# Main_9.net
KiCad netlist of a schematic drawn in Altium Designer
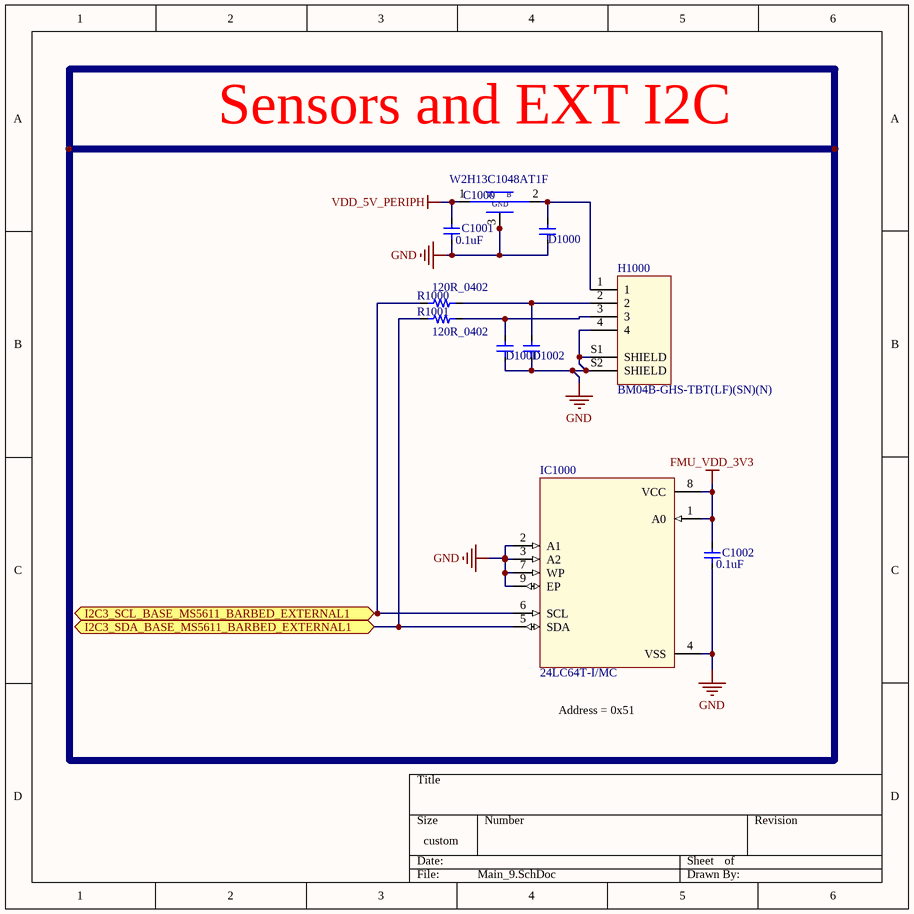
[diagram p0: Main_9.SchDoc]

(export (version "E")
  (design (tool "Eeschema 10.0.6"))
  (components
    (comp (ref "C1000")
      (value "W2H13C1048AT1F")
      (footprint "W2H13C1048AT1F")
      (description "Feed Through Capacitors 25V 0.1uF X7R")
      (libsource (lib "UAV_mainboard") (part "W2H13C1048AT1F"))
    )
    (comp (ref "C1001")
      (value "0.1uF")
      (footprint "C0603")
      (description "CAP CER 0.1UF 25V X7R 0603")
      (libsource (lib "UAV_mainboard") (part "CC0603KRX7R8BB104"))
    )
    (comp (ref "C1002")
      (value "0.1uF")
      (footprint "C0603")
      (description "CAP CER 0.1UF 25V X7R 0603")
      (libsource (lib "UAV_mainboard") (part "CC0603KRX7R8BB104"))
    )
    (comp (ref "D1000")
      (value "PESD0402-140")
      (footprint "PESD0402-140")
      (description "40V Clamp - Ipp Tvs Diode Surface Mount 0402")
      (libsource (lib "UAV_mainboard") (part "PESD0402-140"))
    )
    (comp (ref "D1001")
      (value "PESD0402-140")
      (footprint "PESD0402-140")
      (description "40V Clamp - Ipp Tvs Diode Surface Mount 0402")
      (libsource (lib "UAV_mainboard") (part "PESD0402-140"))
    )
    (comp (ref "D1002")
      (value "PESD0402-140")
      (footprint "PESD0402-140")
      (description "40V Clamp - Ipp Tvs Diode Surface Mount 0402")
      (libsource (lib "UAV_mainboard") (part "PESD0402-140"))
    )
    (comp (ref "H1000")
      (value "BM04B-GHS-TBT(LF)(SN)(N)")
      (footprint "BM04B-GHS-TBT(LF)(SN)(N)")
      (description "Connector Header Surface Mount 4 position 0.049\" (1.25mm)")
      (libsource (lib "UAV_mainboard") (part "BM04B-GHS-TBT(LF)(SN)(N)"))
    )
    (comp (ref "IC1000")
      (value "24LC64T-I/MC")
      (footprint "8DFN")
      (description "IC EEPROM 64KBIT I2C 400KHZ 8DFN")
      (libsource (lib "UAV_mainboard") (part "24LC64T-I/MC"))
    )
    (comp (ref "R1000")
      (value "120R_0402")
      (footprint "R0402")
      (description "120 Ohms ±1% 0.063W, 1/16W Chip Resistor 0402 (1005 Metric) Moisture Resistant Thick Film")
      (libsource (lib "UAV_mainboard") (part "RC0402FR-07120RL"))
    )
    (comp (ref "R1001")
      (value "120R_0402")
      (footprint "R0402")
      (description "120 Ohms ±1% 0.063W, 1/16W Chip Resistor 0402 (1005 Metric) Moisture Resistant Thick Film")
      (libsource (lib "UAV_mainboard") (part "RC0402FR-07120RL"))
    )
  )
  (nets
    (net (code "1") (name "/I2C3_SCL_BASE_MS5611_BARBED_EXTERNAL1") (class "Default")
      (node (ref "IC1000") (pin "6") (pinfunction "SCL_6") (pintype "input"))
      (node (ref "R1000") (pin "1") (pinfunction "1_1") (pintype "passive"))
    )
    (net (code "2") (name "/I2C3_SDA_BASE_MS5611_BARBED_EXTERNAL1") (class "Default")
      (node (ref "IC1000") (pin "5") (pinfunction "SDA_5") (pintype "bidirectional"))
      (node (ref "R1001") (pin "1") (pinfunction "1_1") (pintype "passive"))
    )
    (net (code "3") (name "FMU_VDD_3V3") (class "Default")
      (node (ref "C1002") (pin "2") (pinfunction "2_2") (pintype "passive"))
      (node (ref "IC1000") (pin "1") (pinfunction "A0_1") (pintype "input"))
      (node (ref "IC1000") (pin "8") (pinfunction "VCC_8") (pintype "power_in"))
    )
    (net (code "4") (name "GND") (class "Default")
      (node (ref "C1000") (pin "3") (pintype "passive"))
      (node (ref "C1000") (pin "4") (pinfunction "4_4") (pintype "passive"))
      (node (ref "C1001") (pin "1") (pinfunction "1_1") (pintype "passive"))
      (node (ref "C1002") (pin "1") (pinfunction "1_1") (pintype "passive"))
      (node (ref "D1000") (pin "1") (pinfunction "1_1") (pintype "passive"))
      (node (ref "D1001") (pin "1") (pinfunction "1_1") (pintype "passive"))
      (node (ref "D1002") (pin "1") (pinfunction "1_1") (pintype "passive"))
      (node (ref "H1000") (pin "4") (pinfunction "4_4") (pintype "passive"))
      (node (ref "H1000") (pin "S1") (pinfunction "SHIELD_S1") (pintype "passive"))
      (node (ref "H1000") (pin "S2") (pinfunction "SHIELD_S2") (pintype "passive"))
      (node (ref "IC1000") (pin "2") (pinfunction "A1_2") (pintype "input"))
      (node (ref "IC1000") (pin "3") (pinfunction "A2_3") (pintype "input"))
      (node (ref "IC1000") (pin "4") (pinfunction "VSS_4") (pintype "power_in"))
      (node (ref "IC1000") (pin "7") (pinfunction "WP_7") (pintype "input"))
      (node (ref "IC1000") (pin "9") (pinfunction "EP_9") (pintype "bidirectional"))
    )
    (net (code "5") (name "Net-(C1000-Pad2)") (class "Default")
      (node (ref "C1000") (pin "2") (pintype "passive"))
      (node (ref "D1000") (pin "2") (pinfunction "2_2") (pintype "passive"))
      (node (ref "H1000") (pin "1") (pinfunction "1_1") (pintype "passive"))
    )
    (net (code "6") (name "Net-(D1001-Pad2)") (class "Default")
      (node (ref "D1001") (pin "2") (pinfunction "2_2") (pintype "passive"))
      (node (ref "H1000") (pin "3") (pinfunction "3_3") (pintype "passive"))
      (node (ref "R1001") (pin "2") (pinfunction "2_2") (pintype "passive"))
    )
    (net (code "7") (name "Net-(D1002-Pad2)") (class "Default")
      (node (ref "D1002") (pin "2") (pinfunction "2_2") (pintype "passive"))
      (node (ref "H1000") (pin "2") (pinfunction "2_2") (pintype "passive"))
      (node (ref "R1000") (pin "2") (pinfunction "2_2") (pintype "passive"))
    )
    (net (code "8") (name "VDD_5V_PERIPH") (class "Default")
      (node (ref "C1000") (pin "1") (pintype "passive"))
      (node (ref "C1001") (pin "2") (pinfunction "2_2") (pintype "passive"))
    )
  )
)
